# caculator_schematic.net
KiCad netlist of a schematic drawn in Altium Designer
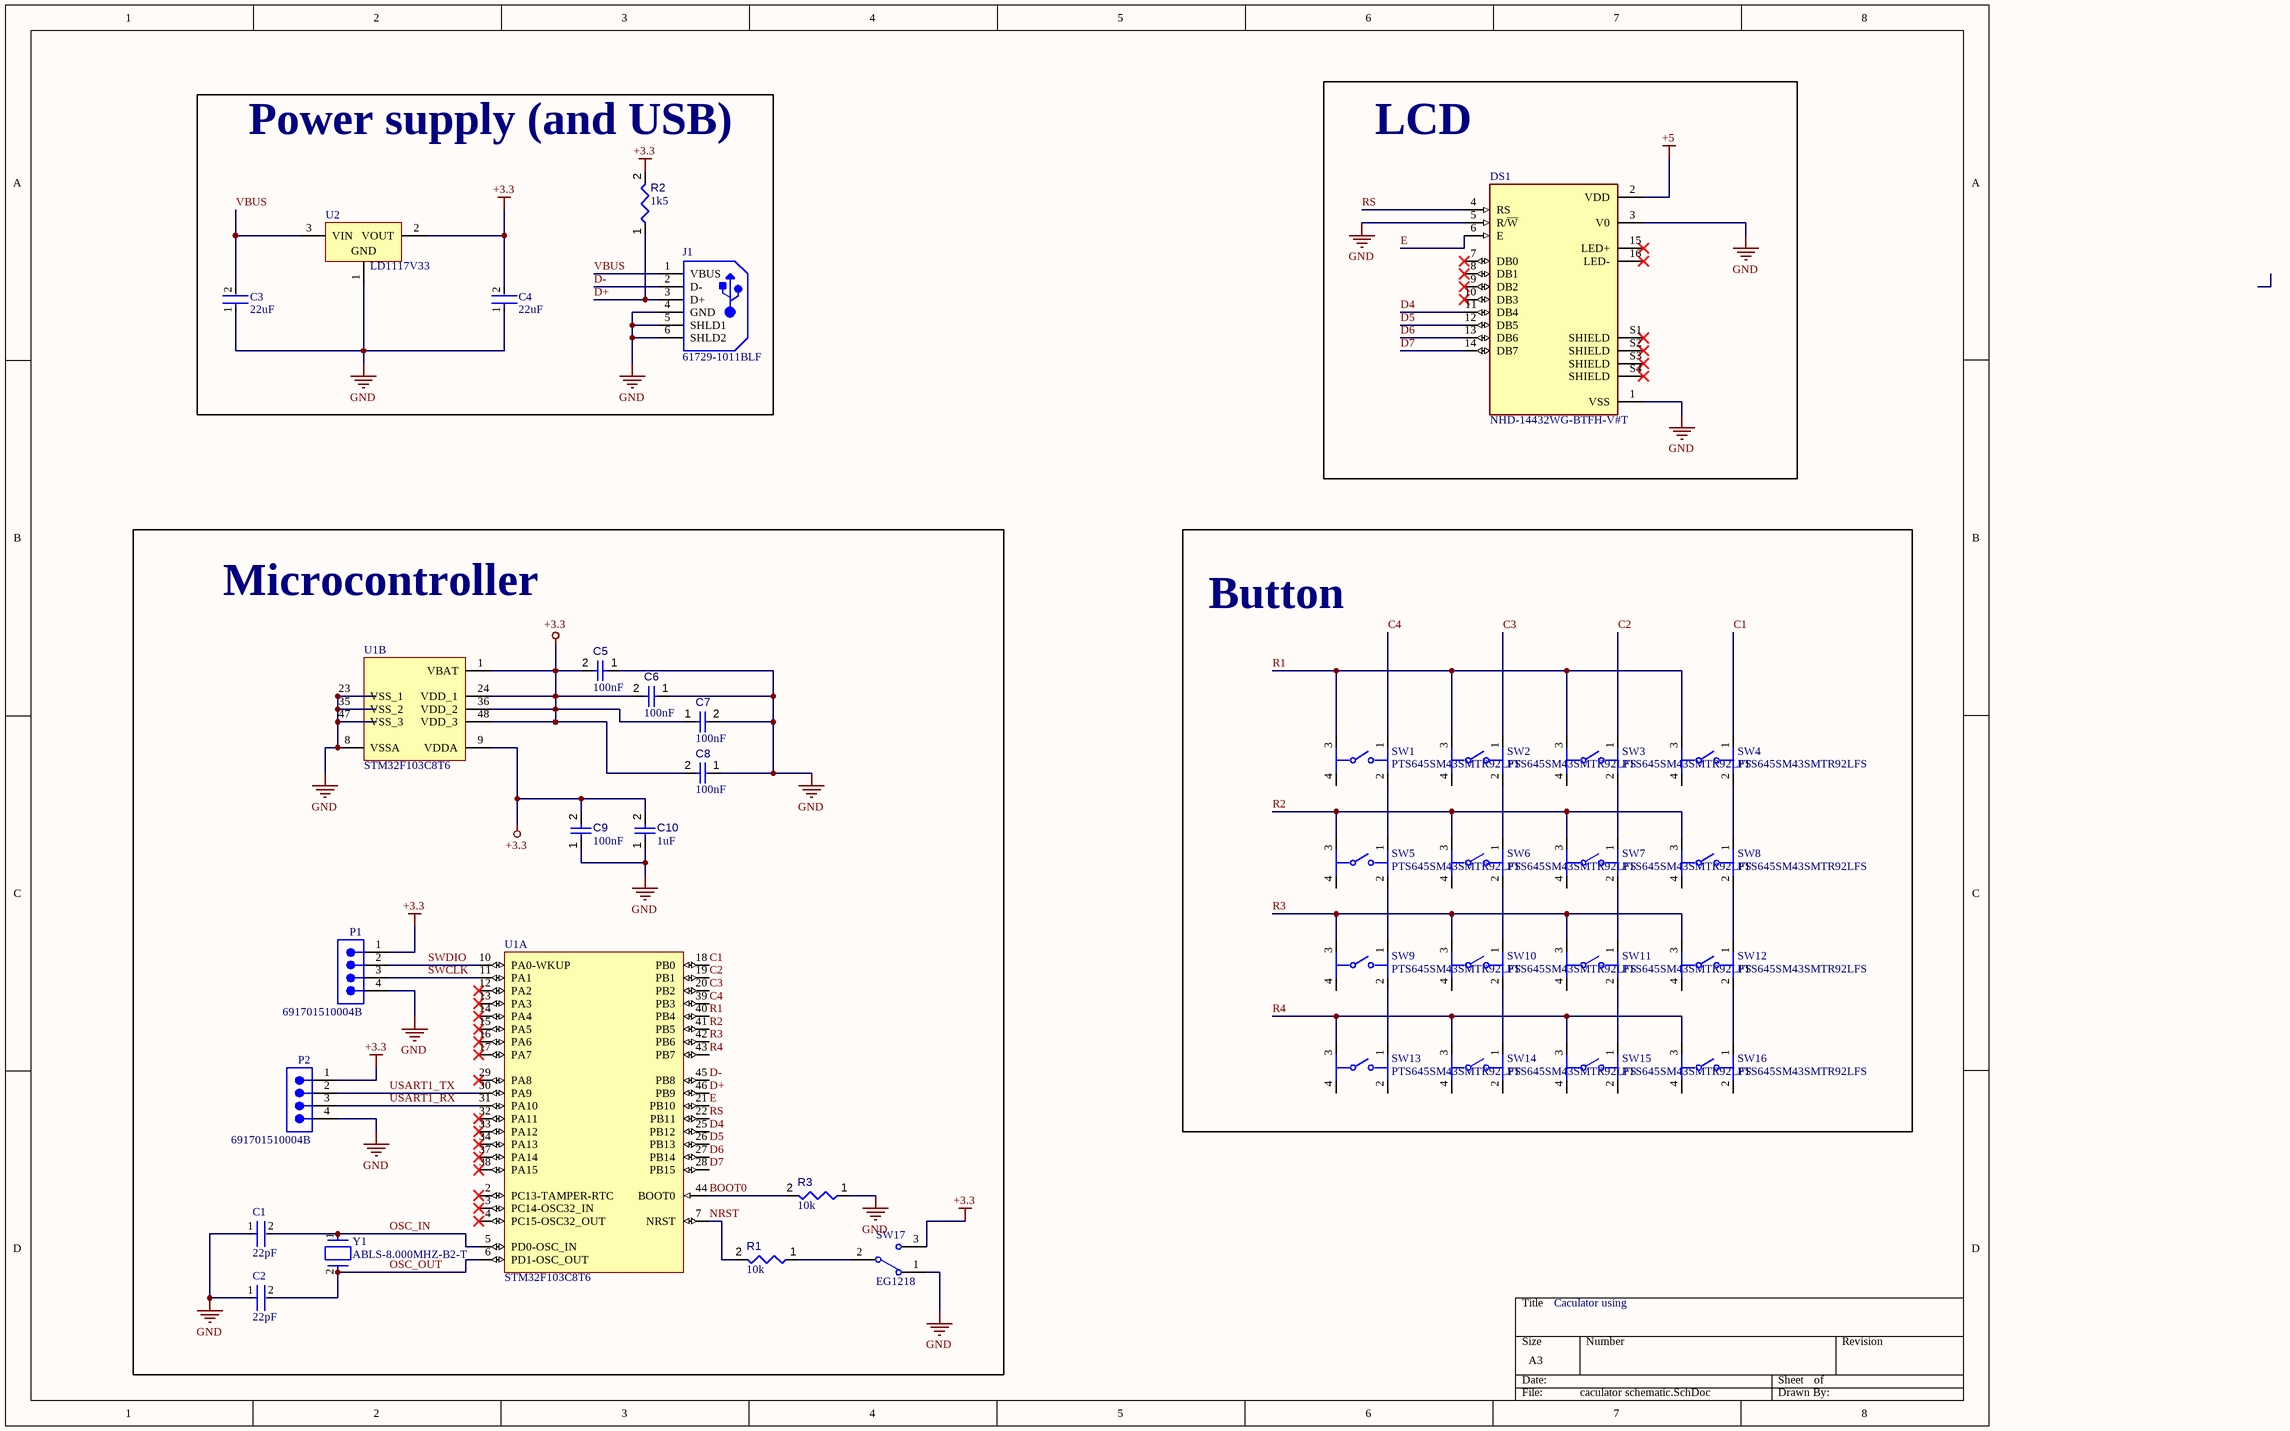
[diagram p0: caculator schematic.SchDoc]

(export (version "E")
  (design (tool "Eeschema 10.0.6"))
  (components
    (comp (ref "C1")
      (value "22pF")
      (footprint "FP-RCE0K1-MFG")
      (description "Cap Ceramic 22pF 50V C0G ±5% Radial 5mm +125°C Automotive Bulk")
      (fields (field (name "TOLERANCE") "5%"))
      (libsource (lib "Altium Content Vault") (part "b4654b650e69147ec39a6b967a45e02"))
    )
    (comp (ref "C2")
      (value "22pF")
      (footprint "FP-RCE0K1-MFG")
      (description "Cap Ceramic 22pF 50V C0G ±5% Radial 5mm +125°C Automotive Bulk")
      (fields (field (name "TOLERANCE") "5%"))
      (libsource (lib "Altium Content Vault") (part "b4654b650e69147ec39a6b967a45e02"))
    )
    (comp (ref "C3")
      (value "22uF")
      (footprint "FP-RCE0K1-MFG")
      (description "Cap Ceramic 22pF 50V C0G ±5% Radial 5mm +125°C Automotive Bulk")
      (fields (field (name "TOLERANCE") "5%"))
      (libsource (lib "Altium Content Vault") (part "b4654b650e69147ec39a6b967a45e02"))
    )
    (comp (ref "C4")
      (value "22uF")
      (footprint "FP-RCE0K1-MFG")
      (description "Cap Ceramic 22pF 50V C0G ±5% Radial 5mm +125°C Automotive Bulk")
      (fields (field (name "TOLERANCE") "5%"))
      (libsource (lib "Altium Content Vault") (part "b4654b650e69147ec39a6b967a45e02"))
    )
    (comp (ref "C5")
      (value "100nF")
      (footprint "CAPC1005X56X25LL10T15")
      (description "Chip Capacitor, 0.1 uF, +/- 5%, 16 V, 0402 (1005 Metric)")
      (fields (field (name "TOLERANCE") "5%") (field (name "Comment") "Capacitor 0.1 uF +/- 5% 16 V 0402"))
      (libsource (lib "Nguyen Thaizeroxz") (part "CAP-NP-2"))
    )
    (comp (ref "C6")
      (value "100nF")
      (footprint "CAPC1005X56X25LL10T15")
      (description "Chip Capacitor, 0.1 uF, +/- 5%, 16 V, 0402 (1005 Metric)")
      (fields (field (name "TOLERANCE") "5%") (field (name "Comment") "Capacitor 0.1 uF +/- 5% 16 V 0402"))
      (libsource (lib "Nguyen Thaizeroxz") (part "CAP-NP-2"))
    )
    (comp (ref "C7")
      (value "100nF")
      (footprint "CAPC1005X56X25LL10T15")
      (description "Chip Capacitor, 0.1 uF, +/- 5%, 16 V, 0402 (1005 Metric)")
      (fields (field (name "TOLERANCE") "5%") (field (name "Comment") "Capacitor 0.1 uF +/- 5% 16 V 0402"))
      (libsource (lib "Nguyen Thaizeroxz") (part "CAP-NP-2"))
    )
    (comp (ref "C8")
      (value "100nF")
      (footprint "CAPC1005X56X25LL10T15")
      (description "Chip Capacitor, 0.1 uF, +/- 5%, 16 V, 0402 (1005 Metric)")
      (fields (field (name "TOLERANCE") "5%") (field (name "Comment") "Capacitor 0.1 uF +/- 5% 16 V 0402"))
      (libsource (lib "Nguyen Thaizeroxz") (part "CAP-NP-2"))
    )
    (comp (ref "C9")
      (value "100nF")
      (footprint "CAPC1005X56X25LL10T15")
      (description "Chip Capacitor, 0.1 uF, +/- 5%, 16 V, 0402 (1005 Metric)")
      (fields (field (name "TOLERANCE") "5%") (field (name "Comment") "Capacitor 0.1 uF +/- 5% 16 V 0402"))
      (libsource (lib "Nguyen Thaizeroxz") (part "CAP-NP-2"))
    )
    (comp (ref "C10")
      (value "1uF")
      (footprint "CAPC1005X56X25LL10T15")
      (description "Chip Capacitor, 0.1 uF, +/- 5%, 16 V, 0402 (1005 Metric)")
      (fields (field (name "TOLERANCE") "5%") (field (name "Comment") "Capacitor 0.1 uF +/- 5% 16 V 0402"))
      (libsource (lib "Nguyen Thaizeroxz") (part "CAP-NP-2"))
    )
    (comp (ref "DS1")
      (value "NHD-14432WG-BTFH-V#T")
      (footprint "LCD_NHD-14432WG-BTFH-V#T")
      (fields (field (name "MF") "Newhaven Display"))
      (libsource (lib "Nguyen Thaizeroxz") (part "NHD-14432WG-BTFH-V#T"))
    )
    (comp (ref "J1")
      (value "61729-1011BLF")
      (footprint "FCI-61729-1011BLF_V")
      (description "USB Receptacle B Type, Right Angle, 4 Position, Height 11.5 mm,-40 to 85 degC, RoHS, Tube")
      (fields (field (name "MANUFACTURER") "FCI Electronics"))
      (libsource (lib "Nguyen Thaizeroxz") (part "USB-4-2SHLD"))
    )
    (comp (ref "P1")
      (value "691701510004B")
      (footprint "691701510004B")
      (description "Terminal Block, 5.08MM, Close Vertical Pcb Header, Thr Type, 4 Pins")
      (libsource (lib "Altium Content Vault") (part "TBL - 1R - 04P - Male"))
    )
    (comp (ref "P2")
      (value "691701510004B")
      (footprint "691701510004B")
      (description "Terminal Block, 5.08MM, Close Vertical Pcb Header, Thr Type, 4 Pins")
      (libsource (lib "Altium Content Vault") (part "TBL - 1R - 04P - Male"))
    )
    (comp (ref "R1")
      (value "10k")
      (footprint "RESC0402(1005)_L")
      (description "Chip Resistor, 1 kOhms, +/-5 %, 63 mW, -55 to 155 degC, 0402")
      (fields (field (name "TOLERANCE") "5%") (field (name "POWER") "63mW"))
      (libsource (lib "Nguyen Thaizeroxz") (part "RES-2"))
    )
    (comp (ref "R2")
      (value "1k5")
      (footprint "RESC0402(1005)_L")
      (description "Chip Resistor, 1 kOhms, +/-5 %, 63 mW, -55 to 155 degC, 0402")
      (fields (field (name "TOLERANCE") "5%") (field (name "POWER") "63mW"))
      (libsource (lib "Nguyen Thaizeroxz") (part "RES-2"))
    )
    (comp (ref "R3")
      (value "10k")
      (footprint "RESC0402(1005)_L")
      (description "Chip Resistor, 1 kOhms, +/-5 %, 63 mW, -55 to 155 degC, 0402")
      (fields (field (name "TOLERANCE") "5%") (field (name "POWER") "63mW"))
      (libsource (lib "Nguyen Thaizeroxz") (part "RES-2"))
    )
    (comp (ref "SW1")
      (value "PTS645SM43SMTR92LFS")
      (footprint "FP-PTS645SM43SMTR92LFS-MFG")
      (description "SWITCH TACTILE SPST-NO 0.05A 12V")
      (libsource (lib "Altium Content Vault") (part "1adf0dd01260c80cf25a44bfd6b99ba"))
    )
    (comp (ref "SW2")
      (value "PTS645SM43SMTR92LFS")
      (footprint "FP-PTS645SM43SMTR92LFS-MFG")
      (description "SWITCH TACTILE SPST-NO 0.05A 12V")
      (libsource (lib "Altium Content Vault") (part "1adf0dd01260c80cf25a44bfd6b99ba"))
    )
    (comp (ref "SW3")
      (value "PTS645SM43SMTR92LFS")
      (footprint "FP-PTS645SM43SMTR92LFS-MFG")
      (description "SWITCH TACTILE SPST-NO 0.05A 12V")
      (libsource (lib "Altium Content Vault") (part "1adf0dd01260c80cf25a44bfd6b99ba"))
    )
    (comp (ref "SW4")
      (value "PTS645SM43SMTR92LFS")
      (footprint "FP-PTS645SM43SMTR92LFS-MFG")
      (description "SWITCH TACTILE SPST-NO 0.05A 12V")
      (libsource (lib "Altium Content Vault") (part "1adf0dd01260c80cf25a44bfd6b99ba"))
    )
    (comp (ref "SW5")
      (value "PTS645SM43SMTR92LFS")
      (footprint "FP-PTS645SM43SMTR92LFS-MFG")
      (description "SWITCH TACTILE SPST-NO 0.05A 12V")
      (libsource (lib "Altium Content Vault") (part "1adf0dd01260c80cf25a44bfd6b99ba"))
    )
    (comp (ref "SW6")
      (value "PTS645SM43SMTR92LFS")
      (footprint "FP-PTS645SM43SMTR92LFS-MFG")
      (description "SWITCH TACTILE SPST-NO 0.05A 12V")
      (libsource (lib "Altium Content Vault") (part "1adf0dd01260c80cf25a44bfd6b99ba"))
    )
    (comp (ref "SW7")
      (value "PTS645SM43SMTR92LFS")
      (footprint "FP-PTS645SM43SMTR92LFS-MFG")
      (description "SWITCH TACTILE SPST-NO 0.05A 12V")
      (libsource (lib "Altium Content Vault") (part "1adf0dd01260c80cf25a44bfd6b99ba"))
    )
    (comp (ref "SW8")
      (value "PTS645SM43SMTR92LFS")
      (footprint "FP-PTS645SM43SMTR92LFS-MFG")
      (description "SWITCH TACTILE SPST-NO 0.05A 12V")
      (libsource (lib "Altium Content Vault") (part "1adf0dd01260c80cf25a44bfd6b99ba"))
    )
    (comp (ref "SW9")
      (value "PTS645SM43SMTR92LFS")
      (footprint "FP-PTS645SM43SMTR92LFS-MFG")
      (description "SWITCH TACTILE SPST-NO 0.05A 12V")
      (libsource (lib "Altium Content Vault") (part "1adf0dd01260c80cf25a44bfd6b99ba"))
    )
    (comp (ref "SW10")
      (value "PTS645SM43SMTR92LFS")
      (footprint "FP-PTS645SM43SMTR92LFS-MFG")
      (description "SWITCH TACTILE SPST-NO 0.05A 12V")
      (libsource (lib "Altium Content Vault") (part "1adf0dd01260c80cf25a44bfd6b99ba"))
    )
    (comp (ref "SW11")
      (value "PTS645SM43SMTR92LFS")
      (footprint "FP-PTS645SM43SMTR92LFS-MFG")
      (description "SWITCH TACTILE SPST-NO 0.05A 12V")
      (libsource (lib "Altium Content Vault") (part "1adf0dd01260c80cf25a44bfd6b99ba"))
    )
    (comp (ref "SW12")
      (value "PTS645SM43SMTR92LFS")
      (footprint "FP-PTS645SM43SMTR92LFS-MFG")
      (description "SWITCH TACTILE SPST-NO 0.05A 12V")
      (libsource (lib "Altium Content Vault") (part "1adf0dd01260c80cf25a44bfd6b99ba"))
    )
    (comp (ref "SW13")
      (value "PTS645SM43SMTR92LFS")
      (footprint "FP-PTS645SM43SMTR92LFS-MFG")
      (description "SWITCH TACTILE SPST-NO 0.05A 12V")
      (libsource (lib "Altium Content Vault") (part "1adf0dd01260c80cf25a44bfd6b99ba"))
    )
    (comp (ref "SW14")
      (value "PTS645SM43SMTR92LFS")
      (footprint "FP-PTS645SM43SMTR92LFS-MFG")
      (description "SWITCH TACTILE SPST-NO 0.05A 12V")
      (libsource (lib "Altium Content Vault") (part "1adf0dd01260c80cf25a44bfd6b99ba"))
    )
    (comp (ref "SW15")
      (value "PTS645SM43SMTR92LFS")
      (footprint "FP-PTS645SM43SMTR92LFS-MFG")
      (description "SWITCH TACTILE SPST-NO 0.05A 12V")
      (libsource (lib "Altium Content Vault") (part "1adf0dd01260c80cf25a44bfd6b99ba"))
    )
    (comp (ref "SW16")
      (value "PTS645SM43SMTR92LFS")
      (footprint "FP-PTS645SM43SMTR92LFS-MFG")
      (description "SWITCH TACTILE SPST-NO 0.05A 12V")
      (libsource (lib "Altium Content Vault") (part "1adf0dd01260c80cf25a44bfd6b99ba"))
    )
    (comp (ref "SW17")
      (value "EG1218")
      (footprint "ESWI-EG1218_V")
      (description "Slide Switch, SPDT, 500 V, -20 to 70 degC, 3-Pin THD, RoHS, Bulk")
      (fields (field (name "MANUFACTURER") "E-Switch"))
      (libsource (lib "Nguyen Thaizeroxz") (part "SW-SPDT-3_B"))
    )
    (comp (ref "U1")
      (value "STM32F103C8T6")
      (footprint "STM-LQFP48_M")
      (description "MCU 32-bit STM32F1 ARM Cortex M3 RISC 64KB Flash 2.5V/3.3V 48-Pin LQFP Tray")
      (libsource (lib "Nguyen Thaizeroxz") (part "MC-ARM-STM32F103X8_B-SQ48"))
    )
    (comp (ref "U2")
      (value "LD1117V33")
      (footprint "STM-TO220-3")
      (fields (field (name "MANUFACTURER") "STMicroelectronics") (field (name "POWER") "12W"))
      (libsource (lib "Nguyen Thaizeroxz") (part "STM-LD1117-V33"))
    )
    (comp (ref "Y1")
      (value "ABLS-8.000MHZ-B2-T")
      (footprint "FP-ABLS-MFG")
      (description "CRYSTAL 8.0000MHZ 18PF SMD")
      (fields (field (name "TOLERANCE") "20ppm"))
      (libsource (lib "Altium Content Vault") (part "c23a69dc6c9e2f18f2079038eb95dd1"))
    )
  )
  (nets
    (net (code "1") (name "+3.3") (class "Default")
      (node (ref "C10") (pin "2") (pinfunction "2_2") (pintype "passive"))
      (node (ref "C4") (pin "2") (pinfunction "2_2") (pintype "passive"))
      (node (ref "C5") (pin "2") (pinfunction "2_2") (pintype "passive"))
      (node (ref "C6") (pin "2") (pinfunction "2_2") (pintype "passive"))
      (node (ref "C7") (pin "1") (pinfunction "1_1") (pintype "passive"))
      (node (ref "C8") (pin "2") (pinfunction "2_2") (pintype "passive"))
      (node (ref "C9") (pin "2") (pinfunction "2_2") (pintype "passive"))
      (node (ref "P1") (pin "1") (pinfunction "1_1") (pintype "passive"))
      (node (ref "P2") (pin "1") (pinfunction "1_1") (pintype "passive"))
      (node (ref "R2") (pin "2") (pinfunction "2_2") (pintype "passive"))
      (node (ref "SW17") (pin "3") (pinfunction "3_3") (pintype "passive"))
      (node (ref "U1") (pin "1") (pinfunction "VBAT_1") (pintype "power_in"))
      (node (ref "U1") (pin "24") (pinfunction "VDD_1_24") (pintype "power_in"))
      (node (ref "U1") (pin "36") (pinfunction "VDD_2_36") (pintype "power_in"))
      (node (ref "U1") (pin "48") (pinfunction "VDD_3_48") (pintype "power_in"))
      (node (ref "U1") (pin "9") (pinfunction "VDDA_9") (pintype "power_in"))
      (node (ref "U2") (pin "2") (pinfunction "VOUT_2") (pintype "power_in"))
    )
    (net (code "2") (name "+5") (class "Default")
      (node (ref "DS1") (pin "2") (pinfunction "VDD_2") (pintype "power_in"))
    )
    (net (code "3") (name "/BOOT0") (class "Default")
      (node (ref "R3") (pin "2") (pinfunction "2_2") (pintype "passive"))
      (node (ref "U1") (pin "44") (pinfunction "BOOT0_44") (pintype "input"))
    )
    (net (code "4") (name "/C1") (class "Default")
      (node (ref "SW4") (pin "1") (pinfunction "1_1") (pintype "passive"))
      (node (ref "U1") (pin "18") (pinfunction "PB0_18") (pintype "bidirectional"))
    )
    (net (code "5") (name "/C2") (class "Default")
      (node (ref "SW3") (pin "1") (pinfunction "1_1") (pintype "passive"))
      (node (ref "U1") (pin "19") (pinfunction "PB1_19") (pintype "bidirectional"))
    )
    (net (code "6") (name "/C3") (class "Default")
      (node (ref "SW2") (pin "1") (pinfunction "1_1") (pintype "passive"))
      (node (ref "U1") (pin "20") (pinfunction "PB2_20") (pintype "bidirectional"))
    )
    (net (code "7") (name "/C4") (class "Default")
      (node (ref "SW1") (pin "1") (pinfunction "1_1") (pintype "passive"))
      (node (ref "U1") (pin "39") (pinfunction "PB3_39") (pintype "bidirectional"))
    )
    (net (code "8") (name "/D+") (class "Default")
      (node (ref "J1") (pin "3") (pinfunction "D+_3") (pintype "passive"))
      (node (ref "R2") (pin "1") (pinfunction "1_1") (pintype "passive"))
      (node (ref "U1") (pin "46") (pinfunction "PB9_46") (pintype "bidirectional"))
    )
    (net (code "9") (name "/D-") (class "Default")
      (node (ref "J1") (pin "2") (pinfunction "D-_2") (pintype "passive"))
      (node (ref "U1") (pin "45") (pinfunction "PB8_45") (pintype "bidirectional"))
    )
    (net (code "10") (name "/D4") (class "Default")
      (node (ref "DS1") (pin "11") (pinfunction "DB4_11") (pintype "bidirectional"))
      (node (ref "U1") (pin "25") (pinfunction "PB12_25") (pintype "bidirectional"))
    )
    (net (code "11") (name "/D5") (class "Default")
      (node (ref "DS1") (pin "12") (pinfunction "DB5_12") (pintype "bidirectional"))
      (node (ref "U1") (pin "26") (pinfunction "PB13_26") (pintype "bidirectional"))
    )
    (net (code "12") (name "/D6") (class "Default")
      (node (ref "DS1") (pin "13") (pinfunction "DB6_13") (pintype "bidirectional"))
      (node (ref "U1") (pin "27") (pinfunction "PB14_27") (pintype "bidirectional"))
    )
    (net (code "13") (name "/D7") (class "Default")
      (node (ref "DS1") (pin "14") (pinfunction "DB7_14") (pintype "bidirectional"))
      (node (ref "U1") (pin "28") (pinfunction "PB15_28") (pintype "bidirectional"))
    )
    (net (code "14") (name "/E") (class "Default")
      (node (ref "DS1") (pin "6") (pinfunction "E_6") (pintype "input"))
      (node (ref "U1") (pin "21") (pinfunction "PB10_21") (pintype "bidirectional"))
    )
    (net (code "15") (name "/NRST") (class "Default")
      (node (ref "R1") (pin "2") (pinfunction "2_2") (pintype "passive"))
      (node (ref "U1") (pin "7") (pinfunction "NRST_7") (pintype "bidirectional"))
    )
    (net (code "16") (name "/OSC_IN") (class "Default")
      (node (ref "C1") (pin "2") (pinfunction "2_2") (pintype "passive"))
      (node (ref "U1") (pin "5") (pinfunction "PD0-OSC_IN_5") (pintype "bidirectional"))
      (node (ref "Y1") (pin "1") (pinfunction "1_1") (pintype "passive"))
    )
    (net (code "17") (name "/OSC_OUT") (class "Default")
      (node (ref "C2") (pin "2") (pinfunction "2_2") (pintype "passive"))
      (node (ref "U1") (pin "6") (pinfunction "PD1-OSC_OUT_6") (pintype "bidirectional"))
      (node (ref "Y1") (pin "2") (pinfunction "2_2") (pintype "passive"))
    )
    (net (code "18") (name "/R1") (class "Default")
      (node (ref "SW1") (pin "3") (pinfunction "3_3") (pintype "passive"))
      (node (ref "SW2") (pin "3") (pinfunction "3_3") (pintype "passive"))
      (node (ref "SW3") (pin "3") (pinfunction "3_3") (pintype "passive"))
      (node (ref "SW4") (pin "3") (pinfunction "3_3") (pintype "passive"))
      (node (ref "U1") (pin "40") (pinfunction "PB4_40") (pintype "bidirectional"))
    )
    (net (code "19") (name "/R2") (class "Default")
      (node (ref "SW5") (pin "3") (pinfunction "3_3") (pintype "passive"))
      (node (ref "SW6") (pin "3") (pinfunction "3_3") (pintype "passive"))
      (node (ref "SW7") (pin "3") (pinfunction "3_3") (pintype "passive"))
      (node (ref "SW8") (pin "3") (pinfunction "3_3") (pintype "passive"))
      (node (ref "U1") (pin "41") (pinfunction "PB5_41") (pintype "bidirectional"))
    )
    (net (code "20") (name "/R3") (class "Default")
      (node (ref "SW10") (pin "3") (pinfunction "3_3") (pintype "passive"))
      (node (ref "SW11") (pin "3") (pinfunction "3_3") (pintype "passive"))
      (node (ref "SW12") (pin "3") (pinfunction "3_3") (pintype "passive"))
      (node (ref "SW9") (pin "3") (pinfunction "3_3") (pintype "passive"))
      (node (ref "U1") (pin "42") (pinfunction "PB6_42") (pintype "bidirectional"))
    )
    (net (code "21") (name "/R4") (class "Default")
      (node (ref "SW13") (pin "3") (pinfunction "3_3") (pintype "passive"))
      (node (ref "SW14") (pin "3") (pinfunction "3_3") (pintype "passive"))
      (node (ref "SW15") (pin "3") (pinfunction "3_3") (pintype "passive"))
      (node (ref "SW16") (pin "3") (pinfunction "3_3") (pintype "passive"))
      (node (ref "U1") (pin "43") (pinfunction "PB7_43") (pintype "bidirectional"))
    )
    (net (code "22") (name "/RS") (class "Default")
      (node (ref "DS1") (pin "4") (pinfunction "RS_4") (pintype "input"))
      (node (ref "U1") (pin "22") (pinfunction "PB11_22") (pintype "bidirectional"))
    )
    (net (code "23") (name "/SWCLK") (class "Default")
      (node (ref "P1") (pin "3") (pinfunction "3_3") (pintype "passive"))
      (node (ref "U1") (pin "11") (pinfunction "PA1_11") (pintype "bidirectional"))
    )
    (net (code "24") (name "/SWDIO") (class "Default")
      (node (ref "P1") (pin "2") (pinfunction "2_2") (pintype "passive"))
      (node (ref "U1") (pin "10") (pinfunction "PA0-WKUP_10") (pintype "bidirectional"))
    )
    (net (code "25") (name "/USART1_RX") (class "Default")
      (node (ref "P2") (pin "3") (pinfunction "3_3") (pintype "passive"))
      (node (ref "U1") (pin "31") (pinfunction "PA10_31") (pintype "bidirectional"))
    )
    (net (code "26") (name "/USART1_TX") (class "Default")
      (node (ref "P2") (pin "2") (pinfunction "2_2") (pintype "passive"))
      (node (ref "U1") (pin "30") (pinfunction "PA9_30") (pintype "bidirectional"))
    )
    (net (code "27") (name "/VBUS") (class "Default")
      (node (ref "C3") (pin "2") (pinfunction "2_2") (pintype "passive"))
      (node (ref "J1") (pin "1") (pinfunction "VBUS_1") (pintype "passive"))
      (node (ref "U2") (pin "3") (pinfunction "VIN_3") (pintype "power_in"))
    )
    (net (code "28") (name "GND") (class "Default")
      (node (ref "C1") (pin "1") (pinfunction "1_1") (pintype "passive"))
      (node (ref "C10") (pin "1") (pinfunction "1_1") (pintype "passive"))
      (node (ref "C2") (pin "1") (pinfunction "1_1") (pintype "passive"))
      (node (ref "C3") (pin "1") (pinfunction "1_1") (pintype "passive"))
      (node (ref "C4") (pin "1") (pinfunction "1_1") (pintype "passive"))
      (node (ref "C5") (pin "1") (pinfunction "1_1") (pintype "passive"))
      (node (ref "C6") (pin "1") (pinfunction "1_1") (pintype "passive"))
      (node (ref "C7") (pin "2") (pinfunction "2_2") (pintype "passive"))
      (node (ref "C8") (pin "1") (pinfunction "1_1") (pintype "passive"))
      (node (ref "C9") (pin "1") (pinfunction "1_1") (pintype "passive"))
      (node (ref "DS1") (pin "1") (pinfunction "VSS_1") (pintype "power_in"))
      (node (ref "DS1") (pin "3") (pinfunction "V0_3") (pintype "passive"))
      (node (ref "DS1") (pin "5") (pinfunction "R/~{W}_5") (pintype "input"))
      (node (ref "J1") (pin "4") (pinfunction "GND_4") (pintype "passive"))
      (node (ref "J1") (pin "5") (pinfunction "SHLD1_5") (pintype "passive"))
      (node (ref "J1") (pin "6") (pinfunction "SHLD2_6") (pintype "passive"))
      (node (ref "P1") (pin "4") (pinfunction "4_4") (pintype "passive"))
      (node (ref "P2") (pin "4") (pinfunction "4_4") (pintype "passive"))
      (node (ref "R3") (pin "1") (pinfunction "1_1") (pintype "passive"))
      (node (ref "SW17") (pin "1") (pinfunction "1_1") (pintype "passive"))
      (node (ref "U1") (pin "23") (pinfunction "VSS_1_23") (pintype "power_in"))
      (node (ref "U1") (pin "35") (pinfunction "VSS_2_35") (pintype "power_in"))
      (node (ref "U1") (pin "47") (pinfunction "VSS_3_47") (pintype "power_in"))
      (node (ref "U1") (pin "8") (pinfunction "VSSA_8") (pintype "power_in"))
      (node (ref "U2") (pin "1") (pinfunction "GND_1") (pintype "power_in"))
    )
    (net (code "29") (name "Net-(SW1-Pad2)") (class "Default")
      (node (ref "SW1") (pin "2") (pinfunction "2_2") (pintype "passive"))
      (node (ref "SW5") (pin "1") (pinfunction "1_1") (pintype "passive"))
    )
    (net (code "30") (name "Net-(SW2-Pad2)") (class "Default")
      (node (ref "SW2") (pin "2") (pinfunction "2_2") (pintype "passive"))
      (node (ref "SW6") (pin "1") (pinfunction "1_1") (pintype "passive"))
    )
    (net (code "31") (name "Net-(SW3-Pad2)") (class "Default")
      (node (ref "SW3") (pin "2") (pinfunction "2_2") (pintype "passive"))
      (node (ref "SW7") (pin "1") (pinfunction "1_1") (pintype "passive"))
    )
    (net (code "32") (name "Net-(SW4-Pad2)") (class "Default")
      (node (ref "SW4") (pin "2") (pinfunction "2_2") (pintype "passive"))
      (node (ref "SW8") (pin "1") (pinfunction "1_1") (pintype "passive"))
    )
    (net (code "33") (name "Net-(SW5-Pad2)") (class "Default")
      (node (ref "SW5") (pin "2") (pinfunction "2_2") (pintype "passive"))
      (node (ref "SW9") (pin "1") (pinfunction "1_1") (pintype "passive"))
    )
    (net (code "34") (name "Net-(SW10-Pad1)") (class "Default")
      (node (ref "SW10") (pin "1") (pinfunction "1_1") (pintype "passive"))
      (node (ref "SW6") (pin "2") (pinfunction "2_2") (pintype "passive"))
    )
    (net (code "35") (name "Net-(SW10-Pad2)") (class "Default")
      (node (ref "SW10") (pin "2") (pinfunction "2_2") (pintype "passive"))
      (node (ref "SW14") (pin "1") (pinfunction "1_1") (pintype "passive"))
    )
    (net (code "36") (name "Net-(SW11-Pad1)") (class "Default")
      (node (ref "SW11") (pin "1") (pinfunction "1_1") (pintype "passive"))
      (node (ref "SW7") (pin "2") (pinfunction "2_2") (pintype "passive"))
    )
    (net (code "37") (name "Net-(SW11-Pad2)") (class "Default")
      (node (ref "SW11") (pin "2") (pinfunction "2_2") (pintype "passive"))
      (node (ref "SW15") (pin "1") (pinfunction "1_1") (pintype "passive"))
    )
    (net (code "38") (name "Net-(SW12-Pad1)") (class "Default")
      (node (ref "SW12") (pin "1") (pinfunction "1_1") (pintype "passive"))
      (node (ref "SW8") (pin "2") (pinfunction "2_2") (pintype "passive"))
    )
    (net (code "39") (name "Net-(SW12-Pad2)") (class "Default")
      (node (ref "SW12") (pin "2") (pinfunction "2_2") (pintype "passive"))
      (node (ref "SW16") (pin "1") (pinfunction "1_1") (pintype "passive"))
    )
    (net (code "40") (name "Net-(SW13-Pad1)") (class "Default")
      (node (ref "SW13") (pin "1") (pinfunction "1_1") (pintype "passive"))
      (node (ref "SW9") (pin "2") (pinfunction "2_2") (pintype "passive"))
    )
    (net (code "41") (name "Net-(SW17-COM)") (class "Default")
      (node (ref "R1") (pin "1") (pinfunction "1_1") (pintype "passive"))
      (node (ref "SW17") (pin "2") (pinfunction "COM_2") (pintype "passive"))
    )
    (net (code "42") (name "unconnected-(DS1-DB0-Pad7)") (class "Default")
      (node (ref "DS1") (pin "7") (pinfunction "DB0_7") (pintype "bidirectional+no_connect"))
    )
    (net (code "43") (name "unconnected-(DS1-DB1-Pad8)") (class "Default")
      (node (ref "DS1") (pin "8") (pinfunction "DB1_8") (pintype "bidirectional+no_connect"))
    )
    (net (code "44") (name "unconnected-(DS1-DB2-Pad9)") (class "Default")
      (node (ref "DS1") (pin "9") (pinfunction "DB2_9") (pintype "bidirectional+no_connect"))
    )
    (net (code "45") (name "unconnected-(DS1-DB3-Pad10)") (class "Default")
      (node (ref "DS1") (pin "10") (pinfunction "DB3_10") (pintype "bidirectional+no_connect"))
    )
    (net (code "46") (name "unconnected-(DS1-LED+-Pad15)") (class "Default")
      (node (ref "DS1") (pin "15") (pinfunction "LED+_15") (pintype "passive+no_connect"))
    )
    (net (code "47") (name "unconnected-(DS1-LED--Pad16)") (class "Default")
      (node (ref "DS1") (pin "16") (pinfunction "LED-_16") (pintype "passive+no_connect"))
    )
    (net (code "48") (name "unconnected-(DS1-SHIELD-PadS1)") (class "Default")
      (node (ref "DS1") (pin "S1") (pinfunction "SHIELD_S1") (pintype "passive+no_connect"))
    )
    (net (code "49") (name "unconnected-(DS1-SHIELD-PadS2)") (class "Default")
      (node (ref "DS1") (pin "S2") (pinfunction "SHIELD_S2") (pintype "passive+no_connect"))
    )
    (net (code "50") (name "unconnected-(DS1-SHIELD-PadS3)") (class "Default")
      (node (ref "DS1") (pin "S3") (pinfunction "SHIELD_S3") (pintype "passive+no_connect"))
    )
    (net (code "51") (name "unconnected-(DS1-SHIELD-PadS4)") (class "Default")
      (node (ref "DS1") (pin "S4") (pinfunction "SHIELD_S4") (pintype "passive+no_connect"))
    )
    (net (code "52") (name "unconnected-(SW1-Pad4)") (class "Default")
      (node (ref "SW1") (pin "4") (pinfunction "4_4") (pintype "passive"))
    )
    (net (code "53") (name "unconnected-(SW2-Pad4)") (class "Default")
      (node (ref "SW2") (pin "4") (pinfunction "4_4") (pintype "passive"))
    )
    (net (code "54") (name "unconnected-(SW3-Pad4)") (class "Default")
      (node (ref "SW3") (pin "4") (pinfunction "4_4") (pintype "passive"))
    )
    (net (code "55") (name "unconnected-(SW4-Pad4)") (class "Default")
      (node (ref "SW4") (pin "4") (pinfunction "4_4") (pintype "passive"))
    )
    (net (code "56") (name "unconnected-(SW5-Pad4)") (class "Default")
      (node (ref "SW5") (pin "4") (pinfunction "4_4") (pintype "passive"))
    )
    (net (code "57") (name "unconnected-(SW6-Pad4)") (class "Default")
      (node (ref "SW6") (pin "4") (pinfunction "4_4") (pintype "passive"))
    )
    (net (code "58") (name "unconnected-(SW7-Pad4)") (class "Default")
      (node (ref "SW7") (pin "4") (pinfunction "4_4") (pintype "passive"))
    )
    (net (code "59") (name "unconnected-(SW8-Pad4)") (class "Default")
      (node (ref "SW8") (pin "4") (pinfunction "4_4") (pintype "passive"))
    )
    (net (code "60") (name "unconnected-(SW9-Pad4)") (class "Default")
      (node (ref "SW9") (pin "4") (pinfunction "4_4") (pintype "passive"))
    )
    (net (code "61") (name "unconnected-(SW10-Pad4)") (class "Default")
      (node (ref "SW10") (pin "4") (pinfunction "4_4") (pintype "passive"))
    )
    (net (code "62") (name "unconnected-(SW11-Pad4)") (class "Default")
      (node (ref "SW11") (pin "4") (pinfunction "4_4") (pintype "passive"))
    )
    (net (code "63") (name "unconnected-(SW12-Pad4)") (class "Default")
      (node (ref "SW12") (pin "4") (pinfunction "4_4") (pintype "passive"))
    )
    (net (code "64") (name "unconnected-(SW13-Pad2)") (class "Default")
      (node (ref "SW13") (pin "2") (pinfunction "2_2") (pintype "passive"))
    )
    (net (code "65") (name "unconnected-(SW13-Pad4)") (class "Default")
      (node (ref "SW13") (pin "4") (pinfunction "4_4") (pintype "passive"))
    )
    (net (code "66") (name "unconnected-(SW14-Pad2)") (class "Default")
      (node (ref "SW14") (pin "2") (pinfunction "2_2") (pintype "passive"))
    )
    (net (code "67") (name "unconnected-(SW14-Pad4)") (class "Default")
      (node (ref "SW14") (pin "4") (pinfunction "4_4") (pintype "passive"))
    )
    (net (code "68") (name "unconnected-(SW15-Pad2)") (class "Default")
      (node (ref "SW15") (pin "2") (pinfunction "2_2") (pintype "passive"))
    )
    (net (code "69") (name "unconnected-(SW15-Pad4)") (class "Default")
      (node (ref "SW15") (pin "4") (pinfunction "4_4") (pintype "passive"))
    )
    (net (code "70") (name "unconnected-(SW16-Pad2)") (class "Default")
      (node (ref "SW16") (pin "2") (pinfunction "2_2") (pintype "passive"))
    )
    (net (code "71") (name "unconnected-(SW16-Pad4)") (class "Default")
      (node (ref "SW16") (pin "4") (pinfunction "4_4") (pintype "passive"))
    )
    (net (code "72") (name "unconnected-(U1A-PA2-Pad12)") (class "Default")
      (node (ref "U1") (pin "12") (pinfunction "PA2_12") (pintype "bidirectional+no_connect"))
    )
    (net (code "73") (name "unconnected-(U1A-PA3-Pad13)") (class "Default")
      (node (ref "U1") (pin "13") (pinfunction "PA3_13") (pintype "bidirectional+no_connect"))
    )
    (net (code "74") (name "unconnected-(U1A-PA4-Pad14)") (class "Default")
      (node (ref "U1") (pin "14") (pinfunction "PA4_14") (pintype "bidirectional+no_connect"))
    )
    (net (code "75") (name "unconnected-(U1A-PA5-Pad15)") (class "Default")
      (node (ref "U1") (pin "15") (pinfunction "PA5_15") (pintype "bidirectional+no_connect"))
    )
    (net (code "76") (name "unconnected-(U1A-PA6-Pad16)") (class "Default")
      (node (ref "U1") (pin "16") (pinfunction "PA6_16") (pintype "bidirectional+no_connect"))
    )
    (net (code "77") (name "unconnected-(U1A-PA7-Pad17)") (class "Default")
      (node (ref "U1") (pin "17") (pinfunction "PA7_17") (pintype "bidirectional+no_connect"))
    )
    (net (code "78") (name "unconnected-(U1A-PA8-Pad29)") (class "Default")
      (node (ref "U1") (pin "29") (pinfunction "PA8_29") (pintype "bidirectional+no_connect"))
    )
    (net (code "79") (name "unconnected-(U1A-PA11-Pad32)") (class "Default")
      (node (ref "U1") (pin "32") (pinfunction "PA11_32") (pintype "bidirectional+no_connect"))
    )
    (net (code "80") (name "unconnected-(U1A-PA12-Pad33)") (class "Default")
      (node (ref "U1") (pin "33") (pinfunction "PA12_33") (pintype "bidirectional+no_connect"))
    )
    (net (code "81") (name "unconnected-(U1A-PA13-Pad34)") (class "Default")
      (node (ref "U1") (pin "34") (pinfunction "PA13_34") (pintype "bidirectional+no_connect"))
    )
    (net (code "82") (name "unconnected-(U1A-PA14-Pad37)") (class "Default")
      (node (ref "U1") (pin "37") (pinfunction "PA14_37") (pintype "bidirectional+no_connect"))
    )
    (net (code "83") (name "unconnected-(U1A-PA15-Pad38)") (class "Default")
      (node (ref "U1") (pin "38") (pinfunction "PA15_38") (pintype "bidirectional+no_connect"))
    )
    (net (code "84") (name "unconnected-(U1A-PC13-TAMPER-RTC-Pad2)") (class "Default")
      (node (ref "U1") (pin "2") (pinfunction "PC13-TAMPER-RTC_2") (pintype "bidirectional+no_connect"))
    )
    (net (code "85") (name "unconnected-(U1A-PC14-OSC32_IN-Pad3)") (class "Default")
      (node (ref "U1") (pin "3") (pinfunction "PC14-OSC32_IN_3") (pintype "bidirectional+no_connect"))
    )
    (net (code "86") (name "unconnected-(U1A-PC15-OSC32_OUT-Pad4)") (class "Default")
      (node (ref "U1") (pin "4") (pinfunction "PC15-OSC32_OUT_4") (pintype "bidirectional+no_connect"))
    )
  )
)
